# slave.net
KiCad netlist of a schematic drawn in EAGLE
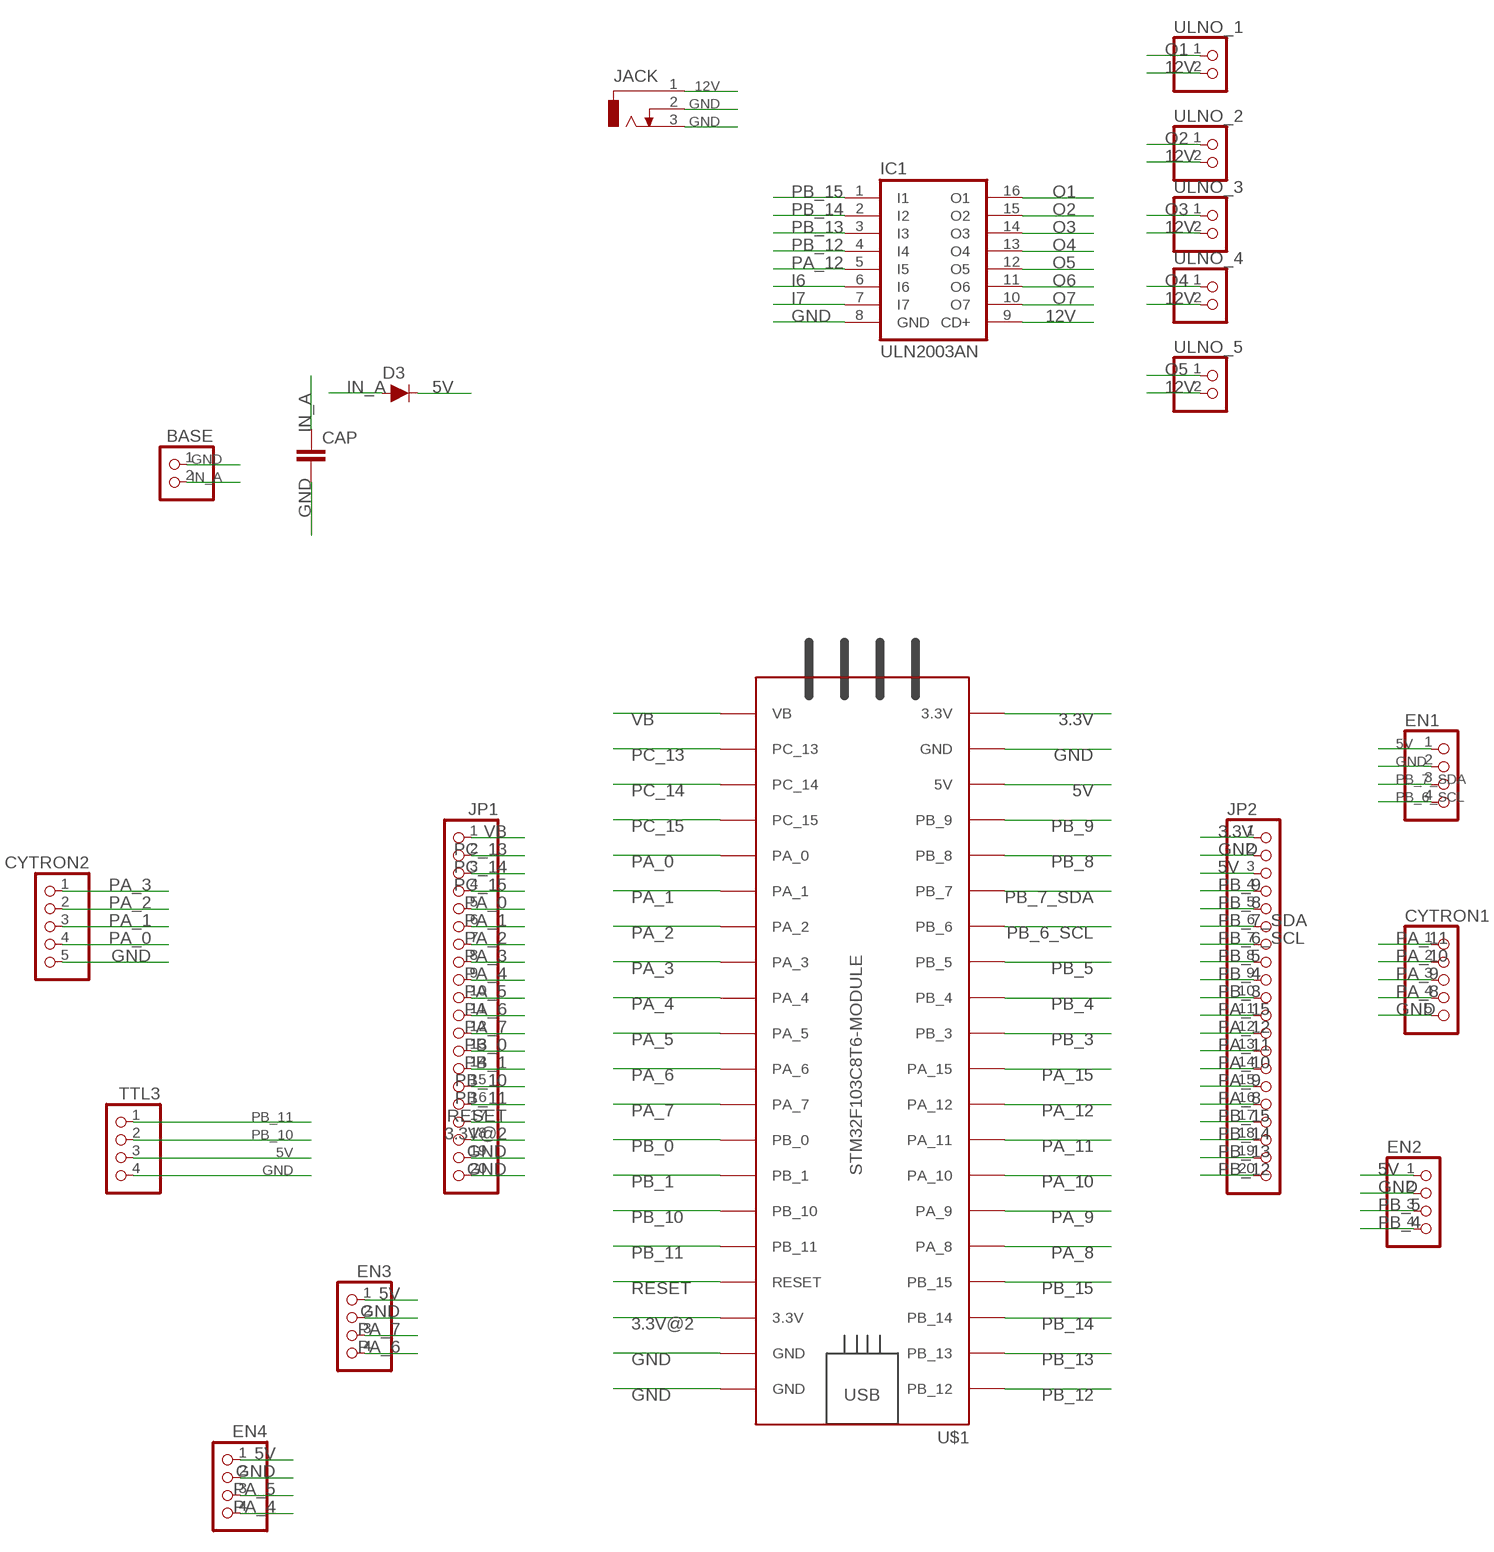
[diagram p0: schematic, sheet 1]

(export (version "E")
  (design (tool "Eeschema 10.0.6"))
  (components
    (comp (ref "BASE")
      (value "PINHD-2_DATA")
      (footprint "eagle-import:1X02_DATA")
      (libsource (lib "eagle-import") (part "PINHD-2_DATA"))
    )
    (comp (ref "CAP")
      (value "CAPACITOR")
      (footprint "eagle-import:C025-025X050")
      (libsource (lib "eagle-import") (part "CAPACITOR"))
    )
    (comp (ref "CYTRON1")
      (value "PINHD-5_DATA")
      (footprint "eagle-import:1X05_DATA")
      (libsource (lib "eagle-import") (part "PINHD-5_DATA"))
    )
    (comp (ref "CYTRON2")
      (value "PINHD-5_DATA")
      (footprint "eagle-import:1X05_DATA")
      (libsource (lib "eagle-import") (part "PINHD-5_DATA"))
    )
    (comp (ref "D3")
      (value "200mA/100V/1V")
      (footprint "eagle-import:DIODE-1N4148")
      (libsource (lib "eagle-import") (part "DIODE(1A)-1N4148"))
    )
    (comp (ref "EN1")
      (value "PINHD-4_DATA")
      (footprint "eagle-import:1X04_DATA")
      (libsource (lib "eagle-import") (part "PINHD-4_DATA"))
    )
    (comp (ref "EN2")
      (value "PINHD-4_DATA")
      (footprint "eagle-import:1X04_DATA")
      (libsource (lib "eagle-import") (part "PINHD-4_DATA"))
    )
    (comp (ref "EN3")
      (value "PINHD-4_DATA")
      (footprint "eagle-import:1X04_DATA")
      (libsource (lib "eagle-import") (part "PINHD-4_DATA"))
    )
    (comp (ref "EN4")
      (value "PINHD-4_DATA")
      (footprint "eagle-import:1X04_DATA")
      (libsource (lib "eagle-import") (part "PINHD-4_DATA"))
    )
    (comp (ref "IC1")
      (value "ULN2003AN")
      (footprint "eagle-import:DIL16")
      (libsource (lib "eagle-import") (part "ULN2003AN"))
    )
    (comp (ref "JACK")
      (value "CON_JACK")
      (footprint "eagle-import:DCJ0303")
      (libsource (lib "eagle-import") (part "CON_JACK"))
    )
    (comp (ref "JP1")
      (value "PINHD-1X20")
      (footprint "eagle-import:1X20")
      (libsource (lib "eagle-import") (part "PINHD-1X20"))
    )
    (comp (ref "JP2")
      (value "PINHD-1X20")
      (footprint "eagle-import:1X20")
      (libsource (lib "eagle-import") (part "PINHD-1X20"))
    )
    (comp (ref "TTL3")
      (value "PINHD-4_DATA")
      (footprint "eagle-import:1X04_DATA")
      (libsource (lib "eagle-import") (part "PINHD-4_DATA"))
    )
    (comp (ref "U$1")
      (value "STM32F103C8T6-MODULE")
      (footprint "eagle-import:STM32F103C8T6-MODULE")
      (libsource (lib "eagle-import") (part "STM32F103C8T6-MODULE"))
    )
    (comp (ref "ULNO_1")
      (value "PINHD-2_DATA")
      (footprint "eagle-import:1X02_DATA")
      (libsource (lib "eagle-import") (part "PINHD-2_DATA"))
    )
    (comp (ref "ULNO_2")
      (value "PINHD-2_DATA")
      (footprint "eagle-import:1X02_DATA")
      (libsource (lib "eagle-import") (part "PINHD-2_DATA"))
    )
    (comp (ref "ULNO_3")
      (value "PINHD-2_DATA")
      (footprint "eagle-import:1X02_DATA")
      (libsource (lib "eagle-import") (part "PINHD-2_DATA"))
    )
    (comp (ref "ULNO_4")
      (value "PINHD-2_DATA")
      (footprint "eagle-import:1X02_DATA")
      (libsource (lib "eagle-import") (part "PINHD-2_DATA"))
    )
    (comp (ref "ULNO_5")
      (value "PINHD-2_DATA")
      (footprint "eagle-import:1X02_DATA")
      (libsource (lib "eagle-import") (part "PINHD-2_DATA"))
    )
  )
  (nets
    (net (code "1") (name "/3.3V") (class "Default")
      (node (ref "JP2") (pin "1") (pinfunction "1_1") (pintype "passive"))
      (node (ref "U$1") (pin "3.3V_1") (pinfunction "3.3V_3.3V_1") (pintype "bidirectional"))
    )
    (net (code "2") (name "/3.3V@2") (class "Default")
      (node (ref "JP1") (pin "18") (pinfunction "18_18") (pintype "passive"))
      (node (ref "U$1") (pin "3.3V_2") (pinfunction "3.3V_3.3V_2") (pintype "bidirectional"))
    )
    (net (code "3") (name "/5V") (class "Default")
      (node (ref "D3") (pin "C") (pinfunction "C_C") (pintype "passive"))
      (node (ref "EN1") (pin "1") (pinfunction "1_1") (pintype "passive"))
      (node (ref "EN2") (pin "1") (pinfunction "1_1") (pintype "passive"))
      (node (ref "EN3") (pin "1") (pinfunction "1_1") (pintype "passive"))
      (node (ref "EN4") (pin "1") (pinfunction "1_1") (pintype "passive"))
      (node (ref "JP2") (pin "3") (pinfunction "3_3") (pintype "passive"))
      (node (ref "TTL3") (pin "3") (pinfunction "3_3") (pintype "passive"))
      (node (ref "U$1") (pin "5V") (pinfunction "5V_5V") (pintype "bidirectional"))
    )
    (net (code "4") (name "/12V") (class "Default")
      (node (ref "IC1") (pin "9") (pinfunction "CD+_9") (pintype "passive"))
      (node (ref "JACK") (pin "1") (pinfunction "1_1") (pintype "passive"))
      (node (ref "ULNO_1") (pin "2") (pinfunction "2_2") (pintype "passive"))
      (node (ref "ULNO_2") (pin "2") (pinfunction "2_2") (pintype "passive"))
      (node (ref "ULNO_3") (pin "2") (pinfunction "2_2") (pintype "passive"))
      (node (ref "ULNO_4") (pin "2") (pinfunction "2_2") (pintype "passive"))
      (node (ref "ULNO_5") (pin "2") (pinfunction "2_2") (pintype "passive"))
    )
    (net (code "5") (name "/GND") (class "Default")
      (node (ref "BASE") (pin "1") (pinfunction "1_1") (pintype "passive"))
      (node (ref "CAP") (pin "2") (pinfunction "2_2") (pintype "passive"))
      (node (ref "CYTRON1") (pin "5") (pinfunction "5_5") (pintype "passive"))
      (node (ref "CYTRON2") (pin "5") (pinfunction "5_5") (pintype "passive"))
      (node (ref "EN1") (pin "2") (pinfunction "2_2") (pintype "passive"))
      (node (ref "EN2") (pin "2") (pinfunction "2_2") (pintype "passive"))
      (node (ref "EN3") (pin "2") (pinfunction "2_2") (pintype "passive"))
      (node (ref "EN4") (pin "2") (pinfunction "2_2") (pintype "passive"))
      (node (ref "IC1") (pin "8") (pinfunction "GND_8") (pintype "power_in"))
      (node (ref "JACK") (pin "2") (pinfunction "2_2") (pintype "passive"))
      (node (ref "JACK") (pin "3") (pinfunction "3_3") (pintype "passive"))
      (node (ref "JP1") (pin "19") (pinfunction "19_19") (pintype "passive"))
      (node (ref "JP1") (pin "20") (pinfunction "20_20") (pintype "passive"))
      (node (ref "JP2") (pin "2") (pinfunction "2_2") (pintype "passive"))
      (node (ref "TTL3") (pin "4") (pinfunction "4_4") (pintype "passive"))
      (node (ref "U$1") (pin "GND_1") (pinfunction "GND_GND_1") (pintype "bidirectional"))
      (node (ref "U$1") (pin "GND_2") (pinfunction "GND_GND_2") (pintype "bidirectional"))
      (node (ref "U$1") (pin "GND_3") (pinfunction "GND_GND_3") (pintype "power_in"))
    )
    (net (code "6") (name "/I6") (class "Default")
      (node (ref "IC1") (pin "6") (pinfunction "I6_6") (pintype "input"))
    )
    (net (code "7") (name "/I7") (class "Default")
      (node (ref "IC1") (pin "7") (pinfunction "I7_7") (pintype "input"))
    )
    (net (code "8") (name "/IN_A") (class "Default")
      (node (ref "BASE") (pin "2") (pinfunction "2_2") (pintype "passive"))
      (node (ref "CAP") (pin "1") (pinfunction "1_1") (pintype "passive"))
      (node (ref "D3") (pin "A") (pinfunction "A_A") (pintype "passive"))
    )
    (net (code "9") (name "/O1") (class "Default")
      (node (ref "IC1") (pin "16") (pinfunction "O1_16") (pintype "open_collector"))
      (node (ref "ULNO_1") (pin "1") (pinfunction "1_1") (pintype "passive"))
    )
    (net (code "10") (name "/O2") (class "Default")
      (node (ref "IC1") (pin "15") (pinfunction "O2_15") (pintype "open_collector"))
      (node (ref "ULNO_2") (pin "1") (pinfunction "1_1") (pintype "passive"))
    )
    (net (code "11") (name "/O3") (class "Default")
      (node (ref "IC1") (pin "14") (pinfunction "O3_14") (pintype "open_collector"))
      (node (ref "ULNO_3") (pin "1") (pinfunction "1_1") (pintype "passive"))
    )
    (net (code "12") (name "/O4") (class "Default")
      (node (ref "IC1") (pin "13") (pinfunction "O4_13") (pintype "open_collector"))
      (node (ref "ULNO_4") (pin "1") (pinfunction "1_1") (pintype "passive"))
    )
    (net (code "13") (name "/O5") (class "Default")
      (node (ref "IC1") (pin "12") (pinfunction "O5_12") (pintype "open_collector"))
      (node (ref "ULNO_5") (pin "1") (pinfunction "1_1") (pintype "passive"))
    )
    (net (code "14") (name "/O6") (class "Default")
      (node (ref "IC1") (pin "11") (pinfunction "O6_11") (pintype "open_collector"))
    )
    (net (code "15") (name "/O7") (class "Default")
      (node (ref "IC1") (pin "10") (pinfunction "O7_10") (pintype "open_collector"))
    )
    (net (code "16") (name "/PA_0") (class "Default")
      (node (ref "CYTRON2") (pin "4") (pinfunction "4_4") (pintype "passive"))
      (node (ref "JP1") (pin "5") (pinfunction "5_5") (pintype "passive"))
      (node (ref "U$1") (pin "PA_0") (pinfunction "PA_0_PA_0") (pintype "bidirectional"))
    )
    (net (code "17") (name "/PA_1") (class "Default")
      (node (ref "CYTRON2") (pin "3") (pinfunction "3_3") (pintype "passive"))
      (node (ref "JP1") (pin "6") (pinfunction "6_6") (pintype "passive"))
      (node (ref "U$1") (pin "PA_1") (pinfunction "PA_1_PA_1") (pintype "bidirectional"))
    )
    (net (code "18") (name "/PA_2") (class "Default")
      (node (ref "CYTRON2") (pin "2") (pinfunction "2_2") (pintype "passive"))
      (node (ref "JP1") (pin "7") (pinfunction "7_7") (pintype "passive"))
      (node (ref "U$1") (pin "PA_2") (pinfunction "PA_2_PA_2") (pintype "bidirectional"))
    )
    (net (code "19") (name "/PA_3") (class "Default")
      (node (ref "CYTRON2") (pin "1") (pinfunction "1_1") (pintype "passive"))
      (node (ref "JP1") (pin "8") (pinfunction "8_8") (pintype "passive"))
      (node (ref "U$1") (pin "PA_3") (pinfunction "PA_3_PA_3") (pintype "bidirectional"))
    )
    (net (code "20") (name "/PA_4") (class "Default")
      (node (ref "EN4") (pin "4") (pinfunction "4_4") (pintype "passive"))
      (node (ref "JP1") (pin "9") (pinfunction "9_9") (pintype "passive"))
      (node (ref "U$1") (pin "PA_4") (pinfunction "PA_4_PA_4") (pintype "bidirectional"))
    )
    (net (code "21") (name "/PA_5") (class "Default")
      (node (ref "EN4") (pin "3") (pinfunction "3_3") (pintype "passive"))
      (node (ref "JP1") (pin "10") (pinfunction "10_10") (pintype "passive"))
      (node (ref "U$1") (pin "PA_5") (pinfunction "PA_5_PA_5") (pintype "bidirectional"))
    )
    (net (code "22") (name "/PA_6") (class "Default")
      (node (ref "EN3") (pin "4") (pinfunction "4_4") (pintype "passive"))
      (node (ref "JP1") (pin "11") (pinfunction "11_11") (pintype "passive"))
      (node (ref "U$1") (pin "PA_6") (pinfunction "PA_6_PA_6") (pintype "bidirectional"))
    )
    (net (code "23") (name "/PA_7") (class "Default")
      (node (ref "EN3") (pin "3") (pinfunction "3_3") (pintype "passive"))
      (node (ref "JP1") (pin "12") (pinfunction "12_12") (pintype "passive"))
      (node (ref "U$1") (pin "PA_7") (pinfunction "PA_7_PA_7") (pintype "bidirectional"))
    )
    (net (code "24") (name "/PA_8") (class "Default")
      (node (ref "CYTRON1") (pin "4") (pinfunction "4_4") (pintype "passive"))
      (node (ref "JP2") (pin "16") (pinfunction "16_16") (pintype "passive"))
      (node (ref "U$1") (pin "PA_8") (pinfunction "PA_8_PA_8") (pintype "bidirectional"))
    )
    (net (code "25") (name "/PA_9") (class "Default")
      (node (ref "CYTRON1") (pin "3") (pinfunction "3_3") (pintype "passive"))
      (node (ref "JP2") (pin "15") (pinfunction "15_15") (pintype "passive"))
      (node (ref "U$1") (pin "PA_9") (pinfunction "PA_9_PA_9") (pintype "bidirectional"))
    )
    (net (code "26") (name "/PA_10") (class "Default")
      (node (ref "CYTRON1") (pin "2") (pinfunction "2_2") (pintype "passive"))
      (node (ref "JP2") (pin "14") (pinfunction "14_14") (pintype "passive"))
      (node (ref "U$1") (pin "PA_10") (pinfunction "PA_10_PA_10") (pintype "bidirectional"))
    )
    (net (code "27") (name "/PA_11") (class "Default")
      (node (ref "CYTRON1") (pin "1") (pinfunction "1_1") (pintype "passive"))
      (node (ref "JP2") (pin "13") (pinfunction "13_13") (pintype "passive"))
      (node (ref "U$1") (pin "PA_11") (pinfunction "PA_11_PA_11") (pintype "bidirectional"))
    )
    (net (code "28") (name "/PA_12") (class "Default")
      (node (ref "IC1") (pin "5") (pinfunction "I5_5") (pintype "input"))
      (node (ref "JP2") (pin "12") (pinfunction "12_12") (pintype "passive"))
      (node (ref "U$1") (pin "PA_12") (pinfunction "PA_12_PA_12") (pintype "bidirectional"))
    )
    (net (code "29") (name "/PA_15") (class "Default")
      (node (ref "JP2") (pin "11") (pinfunction "11_11") (pintype "passive"))
      (node (ref "U$1") (pin "PA_15") (pinfunction "PA_15_PA_15") (pintype "bidirectional"))
    )
    (net (code "30") (name "/PB_0") (class "Default")
      (node (ref "JP1") (pin "13") (pinfunction "13_13") (pintype "passive"))
      (node (ref "U$1") (pin "PB_0") (pinfunction "PB_0_PB_0") (pintype "bidirectional"))
    )
    (net (code "31") (name "/PB_1") (class "Default")
      (node (ref "JP1") (pin "14") (pinfunction "14_14") (pintype "passive"))
      (node (ref "U$1") (pin "PB_1") (pinfunction "PB_1_PB_1") (pintype "bidirectional"))
    )
    (net (code "32") (name "/PB_3") (class "Default")
      (node (ref "JP2") (pin "10") (pinfunction "10_10") (pintype "passive"))
      (node (ref "U$1") (pin "PB_3") (pinfunction "PB_3_PB_3") (pintype "bidirectional"))
    )
    (net (code "33") (name "/PB_4") (class "Default")
      (node (ref "EN2") (pin "4") (pinfunction "4_4") (pintype "passive"))
      (node (ref "JP2") (pin "9") (pinfunction "9_9") (pintype "passive"))
      (node (ref "U$1") (pin "PB_4") (pinfunction "PB_4_PB_4") (pintype "bidirectional"))
    )
    (net (code "34") (name "/PB_5") (class "Default")
      (node (ref "EN2") (pin "3") (pinfunction "3_3") (pintype "passive"))
      (node (ref "JP2") (pin "8") (pinfunction "8_8") (pintype "passive"))
      (node (ref "U$1") (pin "PB_5") (pinfunction "PB_5_PB_5") (pintype "bidirectional"))
    )
    (net (code "35") (name "/PB_6_SCL") (class "Default")
      (node (ref "EN1") (pin "4") (pinfunction "4_4") (pintype "passive"))
      (node (ref "JP2") (pin "7") (pinfunction "7_7") (pintype "passive"))
      (node (ref "U$1") (pin "PB_6") (pinfunction "PB_6_PB_6") (pintype "bidirectional"))
    )
    (net (code "36") (name "/PB_7_SDA") (class "Default")
      (node (ref "EN1") (pin "3") (pinfunction "3_3") (pintype "passive"))
      (node (ref "JP2") (pin "6") (pinfunction "6_6") (pintype "passive"))
      (node (ref "U$1") (pin "PB_7") (pinfunction "PB_7_PB_7") (pintype "bidirectional"))
    )
    (net (code "37") (name "/PB_8") (class "Default")
      (node (ref "JP2") (pin "5") (pinfunction "5_5") (pintype "passive"))
      (node (ref "U$1") (pin "PB_8") (pinfunction "PB_8_PB_8") (pintype "bidirectional"))
    )
    (net (code "38") (name "/PB_9") (class "Default")
      (node (ref "JP2") (pin "4") (pinfunction "4_4") (pintype "passive"))
      (node (ref "U$1") (pin "PB_9") (pinfunction "PB_9_PB_9") (pintype "bidirectional"))
    )
    (net (code "39") (name "/PB_10") (class "Default")
      (node (ref "JP1") (pin "15") (pinfunction "15_15") (pintype "passive"))
      (node (ref "TTL3") (pin "2") (pinfunction "2_2") (pintype "passive"))
      (node (ref "U$1") (pin "PB_10") (pinfunction "PB_10_PB_10") (pintype "bidirectional"))
    )
    (net (code "40") (name "/PB_11") (class "Default")
      (node (ref "JP1") (pin "16") (pinfunction "16_16") (pintype "passive"))
      (node (ref "TTL3") (pin "1") (pinfunction "1_1") (pintype "passive"))
      (node (ref "U$1") (pin "PB_11") (pinfunction "PB_11_PB_11") (pintype "bidirectional"))
    )
    (net (code "41") (name "/PB_12") (class "Default")
      (node (ref "IC1") (pin "4") (pinfunction "I4_4") (pintype "input"))
      (node (ref "JP2") (pin "20") (pinfunction "20_20") (pintype "passive"))
      (node (ref "U$1") (pin "PB_12") (pinfunction "PB_12_PB_12") (pintype "bidirectional"))
    )
    (net (code "42") (name "/PB_13") (class "Default")
      (node (ref "IC1") (pin "3") (pinfunction "I3_3") (pintype "input"))
      (node (ref "JP2") (pin "19") (pinfunction "19_19") (pintype "passive"))
      (node (ref "U$1") (pin "PB_13") (pinfunction "PB_13_PB_13") (pintype "bidirectional"))
    )
    (net (code "43") (name "/PB_14") (class "Default")
      (node (ref "IC1") (pin "2") (pinfunction "I2_2") (pintype "input"))
      (node (ref "JP2") (pin "18") (pinfunction "18_18") (pintype "passive"))
      (node (ref "U$1") (pin "PB_14") (pinfunction "PB_14_PB_14") (pintype "bidirectional"))
    )
    (net (code "44") (name "/PB_15") (class "Default")
      (node (ref "IC1") (pin "1") (pinfunction "I1_1") (pintype "input"))
      (node (ref "JP2") (pin "17") (pinfunction "17_17") (pintype "passive"))
      (node (ref "U$1") (pin "PB_15") (pinfunction "PB_15_PB_15") (pintype "bidirectional"))
    )
    (net (code "45") (name "/PC_13") (class "Default")
      (node (ref "JP1") (pin "2") (pinfunction "2_2") (pintype "passive"))
      (node (ref "U$1") (pin "PC_13") (pinfunction "PC_13_PC_13") (pintype "bidirectional"))
    )
    (net (code "46") (name "/PC_14") (class "Default")
      (node (ref "JP1") (pin "3") (pinfunction "3_3") (pintype "passive"))
      (node (ref "U$1") (pin "PC_14") (pinfunction "PC_14_PC_14") (pintype "bidirectional"))
    )
    (net (code "47") (name "/PC_15") (class "Default")
      (node (ref "JP1") (pin "4") (pinfunction "4_4") (pintype "passive"))
      (node (ref "U$1") (pin "PC_15") (pinfunction "PC_15_PC_15") (pintype "bidirectional"))
    )
    (net (code "48") (name "/RESET") (class "Default")
      (node (ref "JP1") (pin "17") (pinfunction "17_17") (pintype "passive"))
      (node (ref "U$1") (pin "RESET") (pinfunction "RESET_RESET") (pintype "bidirectional"))
    )
    (net (code "49") (name "/VB") (class "Default")
      (node (ref "JP1") (pin "1") (pinfunction "1_1") (pintype "passive"))
      (node (ref "U$1") (pin "VB") (pinfunction "VB_VB") (pintype "bidirectional"))
    )
  )
)
